# LAMEBOY.net
KiCad netlist of a schematic drawn in EAGLE
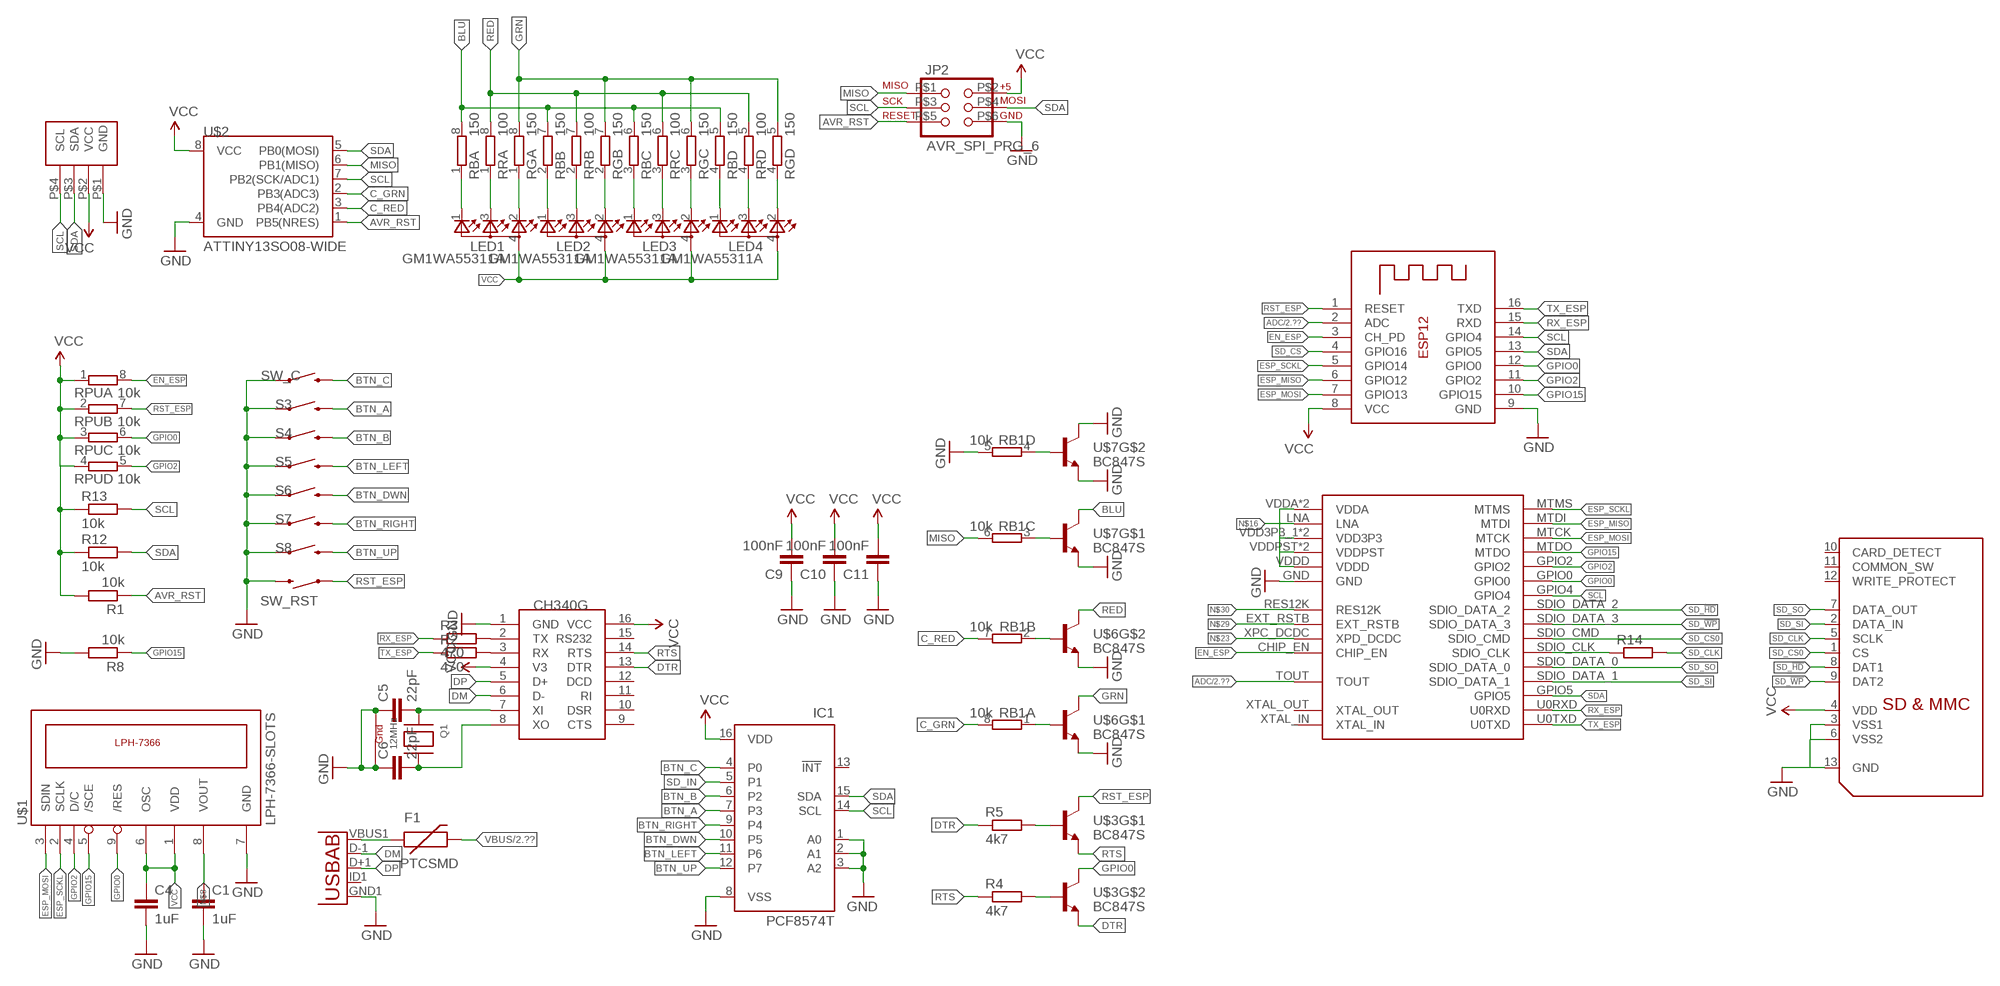
[diagram p0: schematic, sheet 1]
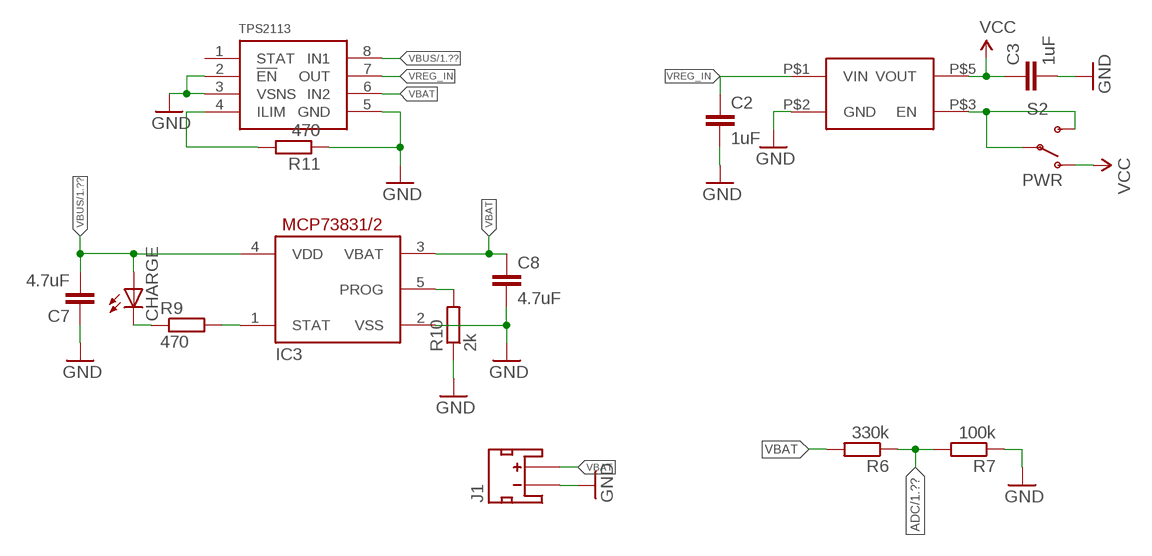
[diagram p1: schematic, sheet 2]

(export (version "E")
  (design (tool "Eeschema 10.0.6"))
  (components
    (comp (ref "C1")
      (value "1uF")
      (footprint "eagle-import:ONEFITSALL")
      (libsource (lib "eagle-import") (part "C-EUONEFITSALL"))
    )
    (comp (ref "C4")
      (value "1uF")
      (footprint "eagle-import:ONEFITSALL")
      (libsource (lib "eagle-import") (part "C-EUONEFITSALL"))
    )
    (comp (ref "C5")
      (value "22pF")
      (footprint "eagle-import:ONEFITSALL")
      (libsource (lib "eagle-import") (part "C-EUONEFITSALL"))
    )
    (comp (ref "C6")
      (value "22pF")
      (footprint "eagle-import:ONEFITSALL")
      (libsource (lib "eagle-import") (part "C-EUONEFITSALL"))
    )
    (comp (ref "C9")
      (value "100nF")
      (footprint "eagle-import:ONEFITSALL")
      (libsource (lib "eagle-import") (part "C-EUONEFITSALL"))
    )
    (comp (ref "C10")
      (value "100nF")
      (footprint "eagle-import:ONEFITSALL")
      (libsource (lib "eagle-import") (part "C-EUONEFITSALL"))
    )
    (comp (ref "C11")
      (value "100nF")
      (footprint "eagle-import:ONEFITSALL")
      (libsource (lib "eagle-import") (part "C-EUONEFITSALL"))
    )
    (comp (ref "CH340G")
      (value "CH340GCH340G")
      (footprint "eagle-import:SOIC16")
      (libsource (lib "eagle-import") (part "CH340GCH340G"))
    )
    (comp (ref "F1")
      (value "PTCSMD")
      (footprint "eagle-import:PTC-1206")
      (libsource (lib "eagle-import") (part "PTCSMD"))
    )
    (comp (ref "IC1")
      (value "PCF8574T")
      (footprint "eagle-import:SO16W")
      (fields (field (name "MPN") "PCF8574T/3,512"))
      (libsource (lib "eagle-import") (part "PCF8574T"))
    )
    (comp (ref "JP2")
      (value "AVR_SPI_PRG_6")
      (footprint "eagle-import:2X3_SMD_PAD")
      (libsource (lib "eagle-import") (part "AVR_SPI_PRG_6"))
    )
    (comp (ref "LED1")
      (value "GM1WA55311A")
      (footprint "eagle-import:GM1WA55311A")
      (libsource (lib "eagle-import") (part "GM1WA55311A"))
    )
    (comp (ref "LED2")
      (value "GM1WA55311A")
      (footprint "eagle-import:GM1WA55311A")
      (libsource (lib "eagle-import") (part "GM1WA55311A"))
    )
    (comp (ref "LED3")
      (value "GM1WA55311A")
      (footprint "eagle-import:GM1WA55311A")
      (libsource (lib "eagle-import") (part "GM1WA55311A"))
    )
    (comp (ref "LED4")
      (value "GM1WA55311A")
      (footprint "eagle-import:GM1WA55311A")
      (libsource (lib "eagle-import") (part "GM1WA55311A"))
    )
    (comp (ref "Q1")
      (value "12MHz")
      (footprint "eagle-import:NX3225_BIGGER")
      (libsource (lib "eagle-import") (part "XTAL-4BIGGER"))
    )
    (comp (ref "R1")
      (value "10k")
      (footprint "eagle-import:ONEFITSALL")
      (libsource (lib "eagle-import") (part "R-EU_ONEFITSALL"))
    )
    (comp (ref "R2")
      (value "470")
      (footprint "eagle-import:ONEFITSALL")
      (libsource (lib "eagle-import") (part "R-EU_ONEFITSALL"))
    )
    (comp (ref "R3")
      (value "470")
      (footprint "eagle-import:ONEFITSALL")
      (libsource (lib "eagle-import") (part "R-EU_ONEFITSALL"))
    )
    (comp (ref "R4")
      (value "4k7")
      (footprint "eagle-import:ONEFITSALL")
      (libsource (lib "eagle-import") (part "R-EU_ONEFITSALL"))
    )
    (comp (ref "R5")
      (value "4k7")
      (footprint "eagle-import:ONEFITSALL")
      (libsource (lib "eagle-import") (part "R-EU_ONEFITSALL"))
    )
    (comp (ref "R8")
      (value "10k")
      (footprint "eagle-import:ONEFITSALL")
      (libsource (lib "eagle-import") (part "R-EU_ONEFITSALL"))
    )
    (comp (ref "R12")
      (value "10k")
      (footprint "eagle-import:ONEFITSALL")
      (libsource (lib "eagle-import") (part "R-EU_ONEFITSALL"))
    )
    (comp (ref "R13")
      (value "10k")
      (footprint "eagle-import:ONEFITSALL")
      (libsource (lib "eagle-import") (part "R-EU_ONEFITSALL"))
    )
    (comp (ref "R14")
      (value "R-EU_R0603")
      (footprint "eagle-import:R0603")
      (libsource (lib "eagle-import") (part "R-EU_R0603"))
    )
    (comp (ref "RB")
      (value "150")
      (footprint "eagle-import:0603-ARC")
      (libsource (lib "eagle-import") (part "4R-N0603-ARC"))
    )
    (comp (ref "RB1")
      (value "10k")
      (footprint "eagle-import:0603-ARC")
      (libsource (lib "eagle-import") (part "4R-N0603-ARC"))
    )
    (comp (ref "RG")
      (value "150")
      (footprint "eagle-import:0603-ARC")
      (libsource (lib "eagle-import") (part "4R-N0603-ARC"))
    )
    (comp (ref "RPU")
      (value "10k")
      (footprint "eagle-import:0603-ARC")
      (libsource (lib "eagle-import") (part "4R-N0603-ARC"))
    )
    (comp (ref "RR")
      (value "100")
      (footprint "eagle-import:0603-ARC")
      (libsource (lib "eagle-import") (part "4R-N0603-ARC"))
    )
    (comp (ref "S3")
      (value "SWITCH-MOMENTARY-2SMD-4")
      (footprint "eagle-import:TACTILE_SWITCH_TALL")
      (libsource (lib "eagle-import") (part "SWITCH-MOMENTARY-2SMD-4"))
    )
    (comp (ref "S4")
      (value "SWITCH-MOMENTARY-2SMD-4")
      (footprint "eagle-import:TACTILE_SWITCH_TALL")
      (libsource (lib "eagle-import") (part "SWITCH-MOMENTARY-2SMD-4"))
    )
    (comp (ref "S5")
      (value "SWITCH-MOMENTARY-2SMD-4")
      (footprint "eagle-import:TACTILE_SWITCH_TALL")
      (libsource (lib "eagle-import") (part "SWITCH-MOMENTARY-2SMD-4"))
    )
    (comp (ref "S6")
      (value "SWITCH-MOMENTARY-2SMD-4")
      (footprint "eagle-import:TACTILE_SWITCH_TALL")
      (libsource (lib "eagle-import") (part "SWITCH-MOMENTARY-2SMD-4"))
    )
    (comp (ref "S7")
      (value "SWITCH-MOMENTARY-2SMD-4")
      (footprint "eagle-import:TACTILE_SWITCH_TALL")
      (libsource (lib "eagle-import") (part "SWITCH-MOMENTARY-2SMD-4"))
    )
    (comp (ref "S8")
      (value "SWITCH-MOMENTARY-2SMD-4")
      (footprint "eagle-import:TACTILE_SWITCH_TALL")
      (libsource (lib "eagle-import") (part "SWITCH-MOMENTARY-2SMD-4"))
    )
    (comp (ref "SW_C")
      (value "SWITCH-MOMENTARY-2-SMD-1101NE")
      (footprint "eagle-import:TACTILE-SWITCH-1101NE")
      (libsource (lib "eagle-import") (part "SWITCH-MOMENTARY-2-SMD-1101NE"))
    )
    (comp (ref "SW_RST")
      (value "SWITCH-MOMENTARY-2-SMD-1101NE")
      (footprint "eagle-import:TACTILE-SWITCH-1101NE")
      (libsource (lib "eagle-import") (part "SWITCH-MOMENTARY-2-SMD-1101NE"))
    )
    (comp (ref "U$1")
      (value "LPH-7366-SLOTS")
      (footprint "eagle-import:LPH-7366-SLOTS")
      (libsource (lib "eagle-import") (part "LPH-7366-SLOTS"))
    )
    (comp (ref "U$2")
      (value "ATTINY13SO08-WIDE")
      (footprint "eagle-import:SO08-EIAJ")
      (libsource (lib "eagle-import") (part "ATTINY13SO08-WIDE"))
    )
    (comp (ref "U$3")
      (value "BC847S")
      (footprint "eagle-import:SOT363")
      (libsource (lib "eagle-import") (part "MMDT3904"))
    )
    (comp (ref "U$6")
      (value "BC847S")
      (footprint "eagle-import:SOT363")
      (libsource (lib "eagle-import") (part "MMDT3904"))
    )
    (comp (ref "U$7")
      (value "BC847S")
      (footprint "eagle-import:SOT363")
      (libsource (lib "eagle-import") (part "MMDT3904"))
    )
    (comp (ref "U$10")
      (value "I2C_GROVE")
      (footprint "eagle-import:I2C_GROVE")
      (libsource (lib "eagle-import") (part "I2C_GROVE"))
    )
    (comp (ref "U$13")
      (value "ESP8266EX")
      (footprint "eagle-import:ESP8266EX")
      (libsource (lib "eagle-import") (part "ESP8266EX"))
    )
    (comp (ref "U$14")
      (value "SDMMCSCDA")
      (footprint "eagle-import:SCDA")
      (libsource (lib "eagle-import") (part "SDMMCSCDA"))
    )
    (comp (ref "U2")
      (value "USB")
      (footprint "eagle-import:USB-AB-MICRO-SMD_V03")
      (libsource (lib "eagle-import") (part "USB-ABCONN-11794"))
    )
    (comp (ref "X1")
      (value "ESP-12")
      (footprint "eagle-import:ESP-12")
      (libsource (lib "eagle-import") (part "ESP-12"))
    )
    (comp (ref "C2")
      (value "1uF")
      (footprint "eagle-import:ONEFITSALL")
      (libsource (lib "eagle-import") (part "C-EUONEFITSALL"))
    )
    (comp (ref "C3")
      (value "1uF")
      (footprint "eagle-import:ONEFITSALL")
      (libsource (lib "eagle-import") (part "C-EUONEFITSALL"))
    )
    (comp (ref "C7")
      (value "4.7uF")
      (footprint "eagle-import:ONEFITSALL")
      (libsource (lib "eagle-import") (part "C-EUONEFITSALL"))
    )
    (comp (ref "C8")
      (value "4.7uF")
      (footprint "eagle-import:ONEFITSALL")
      (libsource (lib "eagle-import") (part "C-EUONEFITSALL"))
    )
    (comp (ref "CHARGE")
      (value "LEDCHIP-LED0805")
      (footprint "eagle-import:CHIP-LED0805")
      (libsource (lib "eagle-import") (part "LEDCHIP-LED0805"))
    )
    (comp (ref "IC3")
      (value "MCP73831")
      (footprint "eagle-import:SOT23-5L")
      (libsource (lib "eagle-import") (part "MCP73831/OT"))
    )
    (comp (ref "J1")
      (value "JST_2MM_MALE")
      (footprint "eagle-import:JST-2-SMD")
      (libsource (lib "eagle-import") (part "JST_2MM_MALE"))
    )
    (comp (ref "R6")
      (value "330k")
      (footprint "eagle-import:ONEFITSALL")
      (libsource (lib "eagle-import") (part "R-EU_ONEFITSALL"))
    )
    (comp (ref "R7")
      (value "100k")
      (footprint "eagle-import:ONEFITSALL")
      (libsource (lib "eagle-import") (part "R-EU_ONEFITSALL"))
    )
    (comp (ref "R9")
      (value "470")
      (footprint "eagle-import:ONEFITSALL")
      (libsource (lib "eagle-import") (part "R-EU_ONEFITSALL"))
    )
    (comp (ref "R10")
      (value "2k")
      (footprint "eagle-import:ONEFITSALL")
      (libsource (lib "eagle-import") (part "R-EU_ONEFITSALL"))
    )
    (comp (ref "R11")
      (value "470")
      (footprint "eagle-import:ONEFITSALL")
      (libsource (lib "eagle-import") (part "R-EU_ONEFITSALL"))
    )
    (comp (ref "S2")
      (value "PWR")
      (footprint "eagle-import:SWITCH-SPST-SMD-A")
      (libsource (lib "eagle-import") (part "SWITCH-SPDT-SMD-A"))
    )
    (comp (ref "U$4")
      (value "TPS2113-PW")
      (footprint "eagle-import:TEXAS-PW")
      (libsource (lib "eagle-import") (part "TPS2113-PW"))
    )
    (comp (ref "U$9")
      (value "AP2112KAP2112K")
      (footprint "eagle-import:AP2112")
      (libsource (lib "eagle-import") (part "AP2112KAP2112K"))
    )
  )
  (nets
    (net (code "1") (name "ADC") (class "Default")
      (node (ref "R6") (pin "P$1") (pinfunction "1_P$1") (pintype "passive"))
      (node (ref "R7") (pin "P$2") (pinfunction "2_P$2") (pintype "passive"))
      (node (ref "U$13") (pin "TOUT") (pinfunction "TOUT_TOUT") (pintype "bidirectional"))
      (node (ref "X1") (pin "2") (pinfunction "ADC_2") (pintype "passive"))
    )
    (net (code "2") (name "AVR_RST") (class "Default")
      (node (ref "JP2") (pin "P$5") (pinfunction "5_P$5") (pintype "passive"))
      (node (ref "R1") (pin "P$1") (pinfunction "1_P$1") (pintype "passive"))
      (node (ref "U$2") (pin "1") (pinfunction "PB5(NRES)_1") (pintype "bidirectional"))
    )
    (net (code "3") (name "BLU") (class "Default")
      (node (ref "RB") (pin "5") (pinfunction "2_5") (pintype "passive"))
      (node (ref "RB") (pin "6") (pinfunction "2_6") (pintype "passive"))
      (node (ref "RB") (pin "7") (pinfunction "2_7") (pintype "passive"))
      (node (ref "RB") (pin "8") (pinfunction "2_8") (pintype "passive"))
      (node (ref "U$7") (pin "3") (pinfunction "C_3") (pintype "passive"))
    )
    (net (code "4") (name "BTN_A") (class "Default")
      (node (ref "IC1") (pin "7") (pinfunction "P3_7") (pintype "bidirectional"))
      (node (ref "S3") (pin "B2") (pinfunction "2_B2") (pintype "passive"))
    )
    (net (code "5") (name "BTN_B") (class "Default")
      (node (ref "IC1") (pin "6") (pinfunction "P2_6") (pintype "bidirectional"))
      (node (ref "S4") (pin "B2") (pinfunction "2_B2") (pintype "passive"))
    )
    (net (code "6") (name "BTN_C") (class "Default")
      (node (ref "IC1") (pin "4") (pinfunction "P0_4") (pintype "bidirectional"))
      (node (ref "SW_C") (pin "P$2") (pinfunction "2_P$2") (pintype "passive"))
    )
    (net (code "7") (name "BTN_DWN") (class "Default")
      (node (ref "IC1") (pin "10") (pinfunction "P5_10") (pintype "bidirectional"))
      (node (ref "S6") (pin "B2") (pinfunction "2_B2") (pintype "passive"))
    )
    (net (code "8") (name "BTN_LEFT") (class "Default")
      (node (ref "IC1") (pin "11") (pinfunction "P6_11") (pintype "bidirectional"))
      (node (ref "S5") (pin "B2") (pinfunction "2_B2") (pintype "passive"))
    )
    (net (code "9") (name "BTN_RIGHT") (class "Default")
      (node (ref "IC1") (pin "9") (pinfunction "P4_9") (pintype "bidirectional"))
      (node (ref "S7") (pin "B2") (pinfunction "2_B2") (pintype "passive"))
    )
    (net (code "10") (name "BTN_UP") (class "Default")
      (node (ref "IC1") (pin "12") (pinfunction "P7_12") (pintype "bidirectional"))
      (node (ref "S8") (pin "B2") (pinfunction "2_B2") (pintype "passive"))
    )
    (net (code "11") (name "C_GRN") (class "Default")
      (node (ref "RB1") (pin "8") (pinfunction "2_8") (pintype "passive"))
      (node (ref "U$2") (pin "2") (pinfunction "PB3(ADC3)_2") (pintype "bidirectional"))
    )
    (net (code "12") (name "C_RED") (class "Default")
      (node (ref "RB1") (pin "7") (pinfunction "2_7") (pintype "passive"))
      (node (ref "U$2") (pin "3") (pinfunction "PB4(ADC2)_3") (pintype "bidirectional"))
    )
    (net (code "13") (name "DM") (class "Default")
      (node (ref "CH340G") (pin "6") (pinfunction "D-_6") (pintype "bidirectional"))
      (node (ref "U2") (pin "D-1") (pinfunction "D-_D-1") (pintype "bidirectional"))
    )
    (net (code "14") (name "DP") (class "Default")
      (node (ref "CH340G") (pin "5") (pinfunction "D+_5") (pintype "bidirectional"))
      (node (ref "U2") (pin "D+1") (pinfunction "D+_D+1") (pintype "bidirectional"))
    )
    (net (code "15") (name "DTR") (class "Default")
      (node (ref "CH340G") (pin "13") (pinfunction "DTR_13") (pintype "bidirectional"))
      (node (ref "R5") (pin "P$1") (pinfunction "1_P$1") (pintype "passive"))
      (node (ref "U$3") (pin "1") (pinfunction "E_1") (pintype "passive"))
    )
    (net (code "16") (name "EN_ESP") (class "Default")
      (node (ref "RPU") (pin "8") (pinfunction "2_8") (pintype "passive"))
      (node (ref "U$13") (pin "CHIP_EN") (pinfunction "CHIP_EN_CHIP_EN") (pintype "bidirectional"))
      (node (ref "X1") (pin "3") (pinfunction "CH_PD_3") (pintype "input"))
    )
    (net (code "17") (name "ESP_MISO") (class "Default")
      (node (ref "U$13") (pin "MTDI") (pinfunction "MTDI_MTDI") (pintype "bidirectional"))
      (node (ref "X1") (pin "6") (pinfunction "GPIO12_6") (pintype "bidirectional"))
    )
    (net (code "18") (name "ESP_MOSI") (class "Default")
      (node (ref "U$1") (pin "3") (pinfunction "SDIN_3") (pintype "input"))
      (node (ref "U$13") (pin "MTCK") (pinfunction "MTCK_MTCK") (pintype "bidirectional"))
      (node (ref "X1") (pin "7") (pinfunction "GPIO13_7") (pintype "bidirectional"))
    )
    (net (code "19") (name "ESP_SCKL") (class "Default")
      (node (ref "U$1") (pin "2") (pinfunction "SCLK_2") (pintype "input"))
      (node (ref "U$13") (pin "MTMS") (pinfunction "MTMS_MTMS") (pintype "bidirectional"))
      (node (ref "X1") (pin "5") (pinfunction "GPIO14_5") (pintype "bidirectional"))
    )
    (net (code "20") (name "GND") (class "Default")
      (node (ref "C1") (pin "P$2") (pinfunction "2_P$2") (pintype "passive"))
      (node (ref "C10") (pin "P$1") (pinfunction "1_P$1") (pintype "passive"))
      (node (ref "C11") (pin "P$1") (pinfunction "1_P$1") (pintype "passive"))
      (node (ref "C2") (pin "P$2") (pinfunction "2_P$2") (pintype "passive"))
      (node (ref "C3") (pin "P$2") (pinfunction "2_P$2") (pintype "passive"))
      (node (ref "C4") (pin "P$2") (pinfunction "2_P$2") (pintype "passive"))
      (node (ref "C5") (pin "P$1") (pinfunction "1_P$1") (pintype "passive"))
      (node (ref "C6") (pin "P$1") (pinfunction "1_P$1") (pintype "passive"))
      (node (ref "C7") (pin "P$1") (pinfunction "1_P$1") (pintype "passive"))
      (node (ref "C8") (pin "P$2") (pinfunction "2_P$2") (pintype "passive"))
      (node (ref "C9") (pin "P$1") (pinfunction "1_P$1") (pintype "passive"))
      (node (ref "CH340G") (pin "1") (pinfunction "GND_1") (pintype "bidirectional"))
      (node (ref "IC1") (pin "1") (pinfunction "A0_1") (pintype "input"))
      (node (ref "IC1") (pin "2") (pinfunction "A1_2") (pintype "input"))
      (node (ref "IC1") (pin "3") (pinfunction "A2_3") (pintype "input"))
      (node (ref "IC1") (pin "8") (pinfunction "VSS_8") (pintype "power_in"))
      (node (ref "IC3") (pin "2") (pinfunction "VSS_2") (pintype "power_in"))
      (node (ref "J1") (pin "1") (pinfunction "-_1") (pintype "bidirectional"))
      (node (ref "JP2") (pin "P$6") (pinfunction "6_P$6") (pintype "passive"))
      (node (ref "Q1") (pin "2") (pinfunction "G2_2") (pintype "power_in"))
      (node (ref "Q1") (pin "4") (pinfunction "G1_4") (pintype "power_in"))
      (node (ref "R10") (pin "P$1") (pinfunction "1_P$1") (pintype "passive"))
      (node (ref "R11") (pin "P$1") (pinfunction "1_P$1") (pintype "passive"))
      (node (ref "R7") (pin "P$1") (pinfunction "1_P$1") (pintype "passive"))
      (node (ref "R8") (pin "P$2") (pinfunction "2_P$2") (pintype "passive"))
      (node (ref "RB1") (pin "5") (pinfunction "2_5") (pintype "passive"))
      (node (ref "S3") (pin "A2") (pinfunction "1_A2") (pintype "passive"))
      (node (ref "S4") (pin "A2") (pinfunction "1_A2") (pintype "passive"))
      (node (ref "S5") (pin "A2") (pinfunction "1_A2") (pintype "passive"))
      (node (ref "S6") (pin "A2") (pinfunction "1_A2") (pintype "passive"))
      (node (ref "S7") (pin "A2") (pinfunction "1_A2") (pintype "passive"))
      (node (ref "S8") (pin "A2") (pinfunction "1_A2") (pintype "passive"))
      (node (ref "SW_C") (pin "P$1") (pinfunction "1_P$1") (pintype "passive"))
      (node (ref "SW_RST") (pin "P$2") (pinfunction "2_P$2") (pintype "passive"))
      (node (ref "U$1") (pin "7") (pinfunction "GND_7") (pintype "power_in"))
      (node (ref "U$10") (pin "P$1") (pinfunction "GND_P$1") (pintype "bidirectional"))
      (node (ref "U$13") (pin "GND") (pinfunction "GND_GND") (pintype "bidirectional"))
      (node (ref "U$14") (pin "13") (pinfunction "GND_13") (pintype "power_in"))
      (node (ref "U$14") (pin "3") (pinfunction "VSS1_3") (pintype "power_in"))
      (node (ref "U$14") (pin "6") (pinfunction "VSS2_6") (pintype "power_in"))
      (node (ref "U$2") (pin "4") (pinfunction "GND_4") (pintype "bidirectional"))
      (node (ref "U$4") (pin "2") (pinfunction "~{EN}_2") (pintype "bidirectional"))
      (node (ref "U$4") (pin "3") (pinfunction "VSNS_3") (pintype "bidirectional"))
      (node (ref "U$4") (pin "5") (pinfunction "GND_5") (pintype "bidirectional"))
      (node (ref "U$6") (pin "1") (pinfunction "E_1") (pintype "passive"))
      (node (ref "U$6") (pin "4") (pinfunction "E_4") (pintype "passive"))
      (node (ref "U$7") (pin "1") (pinfunction "E_1") (pintype "passive"))
      (node (ref "U$7") (pin "4") (pinfunction "E_4") (pintype "passive"))
      (node (ref "U$7") (pin "6") (pinfunction "C_6") (pintype "passive"))
      (node (ref "U$9") (pin "P$2") (pinfunction "GND_P$2") (pintype "bidirectional"))
      (node (ref "U2") (pin "GND1") (pinfunction "GND_GND1") (pintype "bidirectional"))
      (node (ref "X1") (pin "9") (pinfunction "GND_9") (pintype "power_in"))
    )
    (net (code "21") (name "GPIO0") (class "Default")
      (node (ref "RPU") (pin "6") (pinfunction "2_6") (pintype "passive"))
      (node (ref "U$1") (pin "9") (pinfunction "/RES_9") (pintype "input"))
      (node (ref "U$13") (pin "GPIO0") (pinfunction "GPIO0_GPIO0") (pintype "bidirectional"))
      (node (ref "U$3") (pin "6") (pinfunction "C_6") (pintype "passive"))
      (node (ref "X1") (pin "12") (pinfunction "GPIO0_12") (pintype "bidirectional"))
    )
    (net (code "22") (name "GPIO2") (class "Default")
      (node (ref "RPU") (pin "5") (pinfunction "2_5") (pintype "passive"))
      (node (ref "U$1") (pin "4") (pinfunction "D/C_4") (pintype "input"))
      (node (ref "U$13") (pin "GPIO2") (pinfunction "GPIO2_GPIO2") (pintype "bidirectional"))
      (node (ref "X1") (pin "11") (pinfunction "GPIO2_11") (pintype "bidirectional"))
    )
    (net (code "23") (name "GPIO15") (class "Default")
      (node (ref "R8") (pin "P$1") (pinfunction "1_P$1") (pintype "passive"))
      (node (ref "U$1") (pin "5") (pinfunction "/SCE_5") (pintype "input"))
      (node (ref "U$13") (pin "MTDO") (pinfunction "MTDO_MTDO") (pintype "bidirectional"))
      (node (ref "X1") (pin "10") (pinfunction "GPIO15_10") (pintype "bidirectional"))
    )
    (net (code "24") (name "GRN") (class "Default")
      (node (ref "RG") (pin "5") (pinfunction "2_5") (pintype "passive"))
      (node (ref "RG") (pin "6") (pinfunction "2_6") (pintype "passive"))
      (node (ref "RG") (pin "7") (pinfunction "2_7") (pintype "passive"))
      (node (ref "RG") (pin "8") (pinfunction "2_8") (pintype "passive"))
      (node (ref "U$6") (pin "3") (pinfunction "C_3") (pintype "passive"))
    )
    (net (code "25") (name "MISO") (class "Default")
      (node (ref "JP2") (pin "P$1") (pinfunction "1_P$1") (pintype "passive"))
      (node (ref "RB1") (pin "6") (pinfunction "2_6") (pintype "passive"))
      (node (ref "U$2") (pin "6") (pinfunction "PB1(MISO)_6") (pintype "bidirectional"))
    )
    (net (code "26") (name "N$8") (class "Default")
      (node (ref "C1") (pin "P$1") (pinfunction "1_P$1") (pintype "passive"))
      (node (ref "U$1") (pin "8") (pinfunction "VOUT_8") (pintype "passive"))
    )
    (net (code "27") (name "N$16") (class "Default")
      (node (ref "U$13") (pin "LNA") (pinfunction "LNA_LNA") (pintype "bidirectional"))
    )
    (net (code "28") (name "N$23") (class "Default")
      (node (ref "U$13") (pin "XPC_DCDC") (pinfunction "XPD_DCDC_XPC_DCDC") (pintype "bidirectional"))
    )
    (net (code "29") (name "N$29") (class "Default")
      (node (ref "U$13") (pin "EXT_RSTB") (pinfunction "EXT_RSTB_EXT_RSTB") (pintype "bidirectional"))
    )
    (net (code "30") (name "N$30") (class "Default")
      (node (ref "U$13") (pin "RES12K") (pinfunction "RES12K_RES12K") (pintype "bidirectional"))
    )
    (net (code "31") (name "Net-(C5-2)") (class "Default")
      (node (ref "C5") (pin "P$2") (pinfunction "2_P$2") (pintype "passive"))
      (node (ref "CH340G") (pin "7") (pinfunction "XI_7") (pintype "bidirectional"))
      (node (ref "Q1") (pin "1") (pinfunction "X1_1") (pintype "bidirectional"))
    )
    (net (code "32") (name "Net-(C6-2)") (class "Default")
      (node (ref "C6") (pin "P$2") (pinfunction "2_P$2") (pintype "passive"))
      (node (ref "CH340G") (pin "8") (pinfunction "XO_8") (pintype "bidirectional"))
      (node (ref "Q1") (pin "3") (pinfunction "X2_3") (pintype "bidirectional"))
    )
    (net (code "33") (name "Net-(CH340G-RX)") (class "Default")
      (node (ref "CH340G") (pin "3") (pinfunction "RX_3") (pintype "bidirectional"))
      (node (ref "R2") (pin "P$2") (pinfunction "2_P$2") (pintype "passive"))
    )
    (net (code "34") (name "Net-(CH340G-TX)") (class "Default")
      (node (ref "CH340G") (pin "2") (pinfunction "TX_2") (pintype "bidirectional"))
      (node (ref "R3") (pin "P$2") (pinfunction "2_P$2") (pintype "passive"))
    )
    (net (code "35") (name "Net-(IC3-PROG)") (class "Default")
      (node (ref "IC3") (pin "5") (pinfunction "PROG_5") (pintype "input"))
      (node (ref "R10") (pin "P$2") (pinfunction "2_P$2") (pintype "passive"))
    )
    (net (code "36") (name "Net-(IC3-STAT)") (class "Default")
      (node (ref "IC3") (pin "1") (pinfunction "STAT_1") (pintype "output"))
      (node (ref "R9") (pin "P$2") (pinfunction "2_P$2") (pintype "passive"))
    )
    (net (code "37") (name "Net-(LED1-CBLUE)") (class "Default")
      (node (ref "LED1") (pin "3") (pinfunction "CBLUE_3") (pintype "passive"))
      (node (ref "RR") (pin "1") (pinfunction "1_1") (pintype "passive"))
    )
    (net (code "38") (name "Net-(LED1-CGREEN)") (class "Default")
      (node (ref "LED1") (pin "1") (pinfunction "CGREEN_1") (pintype "passive"))
      (node (ref "RB") (pin "1") (pinfunction "1_1") (pintype "passive"))
    )
    (net (code "39") (name "Net-(LED1-CRED)") (class "Default")
      (node (ref "LED1") (pin "2") (pinfunction "CRED_2") (pintype "passive"))
      (node (ref "RG") (pin "1") (pinfunction "1_1") (pintype "passive"))
    )
    (net (code "40") (name "Net-(LED2-CBLUE)") (class "Default")
      (node (ref "LED2") (pin "3") (pinfunction "CBLUE_3") (pintype "passive"))
      (node (ref "RR") (pin "2") (pinfunction "1_2") (pintype "passive"))
    )
    (net (code "41") (name "Net-(LED2-CGREEN)") (class "Default")
      (node (ref "LED2") (pin "1") (pinfunction "CGREEN_1") (pintype "passive"))
      (node (ref "RB") (pin "2") (pinfunction "1_2") (pintype "passive"))
    )
    (net (code "42") (name "Net-(LED2-CRED)") (class "Default")
      (node (ref "LED2") (pin "2") (pinfunction "CRED_2") (pintype "passive"))
      (node (ref "RG") (pin "2") (pinfunction "1_2") (pintype "passive"))
    )
    (net (code "43") (name "Net-(LED3-CBLUE)") (class "Default")
      (node (ref "LED3") (pin "3") (pinfunction "CBLUE_3") (pintype "passive"))
      (node (ref "RR") (pin "3") (pinfunction "1_3") (pintype "passive"))
    )
    (net (code "44") (name "Net-(LED3-CGREEN)") (class "Default")
      (node (ref "LED3") (pin "1") (pinfunction "CGREEN_1") (pintype "passive"))
      (node (ref "RB") (pin "3") (pinfunction "1_3") (pintype "passive"))
    )
    (net (code "45") (name "Net-(LED3-CRED)") (class "Default")
      (node (ref "LED3") (pin "2") (pinfunction "CRED_2") (pintype "passive"))
      (node (ref "RG") (pin "3") (pinfunction "1_3") (pintype "passive"))
    )
    (net (code "46") (name "Net-(LED4-CBLUE)") (class "Default")
      (node (ref "LED4") (pin "3") (pinfunction "CBLUE_3") (pintype "passive"))
      (node (ref "RR") (pin "4") (pinfunction "1_4") (pintype "passive"))
    )
    (net (code "47") (name "Net-(LED4-CGREEN)") (class "Default")
      (node (ref "LED4") (pin "1") (pinfunction "CGREEN_1") (pintype "passive"))
      (node (ref "RB") (pin "4") (pinfunction "1_4") (pintype "passive"))
    )
    (net (code "48") (name "Net-(LED4-CRED)") (class "Default")
      (node (ref "LED4") (pin "2") (pinfunction "CRED_2") (pintype "passive"))
      (node (ref "RG") (pin "4") (pinfunction "1_4") (pintype "passive"))
    )
    (net (code "49") (name "Net-(R4-2)") (class "Default")
      (node (ref "R4") (pin "P$2") (pinfunction "2_P$2") (pintype "passive"))
      (node (ref "U$3") (pin "2") (pinfunction "B_2") (pintype "passive"))
    )
    (net (code "50") (name "Net-(R5-2)") (class "Default")
      (node (ref "R5") (pin "P$2") (pinfunction "2_P$2") (pintype "passive"))
      (node (ref "U$3") (pin "5") (pinfunction "B_5") (pintype "passive"))
    )
    (net (code "51") (name "Net-(R9-1)") (class "Default")
      (node (ref "CHARGE") (pin "C") (pinfunction "C_C") (pintype "passive"))
      (node (ref "R9") (pin "P$1") (pinfunction "1_P$1") (pintype "passive"))
    )
    (net (code "52") (name "Net-(R11-2)") (class "Default")
      (node (ref "R11") (pin "P$2") (pinfunction "2_P$2") (pintype "passive"))
      (node (ref "U$4") (pin "4") (pinfunction "ILIM_4") (pintype "bidirectional"))
    )
    (net (code "53") (name "Net-(R14-Pad1)") (class "Default")
      (node (ref "R14") (pin "1") (pinfunction "1_1") (pintype "passive"))
      (node (ref "U$13") (pin "SDIO_CLK") (pinfunction "SDIO_CLK_SDIO_CLK") (pintype "bidirectional"))
    )
    (net (code "54") (name "Net-(RB1B-1)") (class "Default")
      (node (ref "RB1") (pin "2") (pinfunction "1_2") (pintype "passive"))
      (node (ref "U$6") (pin "2") (pinfunction "B_2") (pintype "passive"))
    )
    (net (code "55") (name "Net-(RB1C-1)") (class "Default")
      (node (ref "RB1") (pin "3") (pinfunction "1_3") (pintype "passive"))
      (node (ref "U$7") (pin "5") (pinfunction "B_5") (pintype "passive"))
    )
    (net (code "56") (name "Net-(RB1D-1)") (class "Default")
      (node (ref "RB1") (pin "4") (pinfunction "1_4") (pintype "passive"))
      (node (ref "U$7") (pin "2") (pinfunction "B_2") (pintype "passive"))
    )
    (net (code "57") (name "Net-(S2-P)") (class "Default")
      (node (ref "S2") (pin "2") (pinfunction "P_2") (pintype "passive"))
      (node (ref "S2") (pin "3") (pinfunction "S_3") (pintype "passive"))
      (node (ref "U$9") (pin "P$3") (pinfunction "EN_P$3") (pintype "bidirectional"))
    )
    (net (code "58") (name "Net-(U$6A-B)") (class "Default")
      (node (ref "RB1") (pin "1") (pinfunction "1_1") (pintype "passive"))
      (node (ref "U$6") (pin "5") (pinfunction "B_5") (pintype "passive"))
    )
    (net (code "59") (name "Net-(U$13-PadVDDA)") (class "Default")
      (node (ref "U$13") (pin "VDD3P3_1") (pinfunction "VDD3P3_VDD3P3_1") (pintype "bidirectional"))
      (node (ref "U$13") (pin "VDD3P3_2") (pinfunction "VDD3P3_VDD3P3_2") (pintype "bidirectional"))
      (node (ref "U$13") (pin "VDDA") (pinfunction "VDDA_VDDA") (pintype "bidirectional"))
      (node (ref "U$13") (pin "VDDA_2") (pinfunction "VDDA_VDDA_2") (pintype "bidirectional"))
      (node (ref "U$13") (pin "VDDD") (pinfunction "VDDD_VDDD") (pintype "bidirectional"))
      (node (ref "U$13") (pin "VDDPST") (pinfunction "VDDPST_VDDPST") (pintype "bidirectional"))
      (node (ref "U$13") (pin "VDDPST_2") (pinfunction "VDDPST_VDDPST_2") (pintype "bidirectional"))
    )
    (net (code "60") (name "Net-(U2-VBUS)") (class "Default")
      (node (ref "F1") (pin "1") (pinfunction "1_1") (pintype "bidirectional"))
      (node (ref "U2") (pin "VBUS1") (pinfunction "VBUS_VBUS1") (pintype "bidirectional"))
    )
    (net (code "61") (name "RED") (class "Default")
      (node (ref "RR") (pin "5") (pinfunction "2_5") (pintype "passive"))
      (node (ref "RR") (pin "6") (pinfunction "2_6") (pintype "passive"))
      (node (ref "RR") (pin "7") (pinfunction "2_7") (pintype "passive"))
      (node (ref "RR") (pin "8") (pinfunction "2_8") (pintype "passive"))
      (node (ref "U$6") (pin "6") (pinfunction "C_6") (pintype "passive"))
    )
    (net (code "62") (name "RST_ESP") (class "Default")
      (node (ref "RPU") (pin "7") (pinfunction "2_7") (pintype "passive"))
      (node (ref "SW_RST") (pin "P$1") (pinfunction "1_P$1") (pintype "passive"))
      (node (ref "U$3") (pin "3") (pinfunction "C_3") (pintype "passive"))
      (node (ref "X1") (pin "1") (pinfunction "RESET_1") (pintype "input"))
    )
    (net (code "63") (name "RTS") (class "Default")
      (node (ref "CH340G") (pin "14") (pinfunction "RTS_14") (pintype "bidirectional"))
      (node (ref "R4") (pin "P$1") (pinfunction "1_P$1") (pintype "passive"))
      (node (ref "U$3") (pin "4") (pinfunction "E_4") (pintype "passive"))
    )
    (net (code "64") (name "RX_ESP") (class "Default")
      (node (ref "R3") (pin "P$1") (pinfunction "1_P$1") (pintype "passive"))
      (node (ref "U$13") (pin "U0RXD") (pinfunction "U0RXD_U0RXD") (pintype "bidirectional"))
      (node (ref "X1") (pin "15") (pinfunction "RXD_15") (pintype "input"))
    )
    (net (code "65") (name "SCL") (class "Default")
      (node (ref "IC1") (pin "14") (pinfunction "SCL_14") (pintype "input"))
      (node (ref "JP2") (pin "P$3") (pinfunction "3_P$3") (pintype "passive"))
      (node (ref "R13") (pin "P$2") (pinfunction "2_P$2") (pintype "passive"))
      (node (ref "U$10") (pin "P$4") (pinfunction "SCL_P$4") (pintype "bidirectional"))
      (node (ref "U$13") (pin "GPIO4") (pinfunction "GPIO4_GPIO4") (pintype "bidirectional"))
      (node (ref "U$2") (pin "7") (pinfunction "PB2(SCK/ADC1)_7") (pintype "bidirectional"))
      (node (ref "X1") (pin "14") (pinfunction "GPIO4_14") (pintype "bidirectional"))
    )
    (net (code "66") (name "SDA") (class "Default")
      (node (ref "IC1") (pin "15") (pinfunction "SDA_15") (pintype "bidirectional"))
      (node (ref "JP2") (pin "P$4") (pinfunction "4_P$4") (pintype "passive"))
      (node (ref "R12") (pin "P$2") (pinfunction "2_P$2") (pintype "passive"))
      (node (ref "U$10") (pin "P$3") (pinfunction "SDA_P$3") (pintype "bidirectional"))
      (node (ref "U$13") (pin "GPIO5") (pinfunction "GPIO5_GPIO5") (pintype "bidirectional"))
      (node (ref "U$2") (pin "5") (pinfunction "PB0(MOSI)_5") (pintype "bidirectional"))
      (node (ref "X1") (pin "13") (pinfunction "GPIO5_13") (pintype "bidirectional"))
    )
    (net (code "67") (name "SD_CLK") (class "Default")
      (node (ref "R14") (pin "2") (pinfunction "2_2") (pintype "passive"))
      (node (ref "U$14") (pin "5") (pinfunction "SCLK_5") (pintype "input"))
    )
    (net (code "68") (name "SD_CS") (class "Default")
      (node (ref "X1") (pin "4") (pinfunction "GPIO16_4") (pintype "bidirectional"))
    )
    (net (code "69") (name "SD_CS0") (class "Default")
      (node (ref "U$13") (pin "SDIO_CMD") (pinfunction "SDIO_CMD_SDIO_CMD") (pintype "bidirectional"))
      (node (ref "U$14") (pin "1") (pinfunction "CS_1") (pintype "input"))
    )
    (net (code "70") (name "SD_IN") (class "Default")
      (node (ref "IC1") (pin "5") (pinfunction "P1_5") (pintype "bidirectional"))
    )
    (net (code "71") (name "SD_SI") (class "Default")
      (node (ref "U$13") (pin "SDIO_DATA_1") (pinfunction "SDIO_DATA_1_SDIO_DATA_1") (pintype "bidirectional"))
      (node (ref "U$14") (pin "2") (pinfunction "DATA_IN_2") (pintype "input"))
    )
    (net (code "72") (name "SD_SO") (class "Default")
      (node (ref "U$13") (pin "SDIO_DATA_0") (pinfunction "SDIO_DATA_0_SDIO_DATA_0") (pintype "bidirectional"))
      (node (ref "U$14") (pin "7") (pinfunction "DATA_OUT_7") (pintype "output"))
    )
    (net (code "73") (name "SD_~{HD}") (class "Default")
      (node (ref "U$13") (pin "SDIO_DATA_2") (pinfunction "SDIO_DATA_2_SDIO_DATA_2") (pintype "bidirectional"))
      (node (ref "U$14") (pin "8") (pinfunction "DAT1_8") (pintype "bidirectional"))
    )
    (net (code "74") (name "SD_~{WP}") (class "Default")
      (node (ref "U$13") (pin "SDIO_DATA_3") (pinfunction "SDIO_DATA_3_SDIO_DATA_3") (pintype "bidirectional"))
      (node (ref "U$14") (pin "9") (pinfunction "DAT2_9") (pintype "bidirectional"))
    )
    (net (code "75") (name "TX_ESP") (class "Default")
      (node (ref "R2") (pin "P$1") (pinfunction "1_P$1") (pintype "passive"))
      (node (ref "U$13") (pin "U0TXD") (pinfunction "U0TXD_U0TXD") (pintype "bidirectional"))
      (node (ref "X1") (pin "16") (pinfunction "TXD_16") (pintype "output"))
    )
    (net (code "76") (name "VBAT") (class "Default")
      (node (ref "C8") (pin "P$1") (pinfunction "1_P$1") (pintype "passive"))
      (node (ref "IC3") (pin "3") (pinfunction "VBAT_3") (pintype "bidirectional"))
      (node (ref "J1") (pin "2") (pinfunction "+_2") (pintype "bidirectional"))
      (node (ref "R6") (pin "P$2") (pinfunction "2_P$2") (pintype "passive"))
      (node (ref "U$4") (pin "6") (pinfunction "IN2_6") (pintype "bidirectional"))
    )
    (net (code "77") (name "VBUS") (class "Default")
      (node (ref "C7") (pin "P$2") (pinfunction "2_P$2") (pintype "passive"))
      (node (ref "CHARGE") (pin "A") (pinfunction "A_A") (pintype "passive"))
      (node (ref "F1") (pin "2") (pinfunction "2_2") (pintype "bidirectional"))
      (node (ref "IC3") (pin "4") (pinfunction "VDD_4") (pintype "power_in"))
      (node (ref "U$4") (pin "8") (pinfunction "IN1_8") (pintype "bidirectional"))
    )
    (net (code "78") (name "VCC") (class "Default")
      (node (ref "C10") (pin "P$2") (pinfunction "2_P$2") (pintype "passive"))
      (node (ref "C11") (pin "P$2") (pinfunction "2_P$2") (pintype "passive"))
      (node (ref "C3") (pin "P$1") (pinfunction "1_P$1") (pintype "passive"))
      (node (ref "C4") (pin "P$1") (pinfunction "1_P$1") (pintype "passive"))
      (node (ref "C9") (pin "P$2") (pinfunction "2_P$2") (pintype "passive"))
      (node (ref "CH340G") (pin "16") (pinfunction "VCC_16") (pintype "bidirectional"))
      (node (ref "CH340G") (pin "4") (pinfunction "V3_4") (pintype "bidirectional"))
      (node (ref "IC1") (pin "16") (pinfunction "VDD_16") (pintype "power_in"))
      (node (ref "JP2") (pin "P$2") (pinfunction "2_P$2") (pintype "passive"))
      (node (ref "LED1") (pin "4") (pinfunction "A_4") (pintype "passive"))
      (node (ref "LED2") (pin "4") (pinfunction "A_4") (pintype "passive"))
      (node (ref "LED3") (pin "4") (pinfunction "A_4") (pintype "passive"))
      (node (ref "LED4") (pin "4") (pinfunction "A_4") (pintype "passive"))
      (node (ref "R1") (pin "P$2") (pinfunction "2_P$2") (pintype "passive"))
      (node (ref "R12") (pin "P$1") (pinfunction "1_P$1") (pintype "passive"))
      (node (ref "R13") (pin "P$1") (pinfunction "1_P$1") (pintype "passive"))
      (node (ref "RPU") (pin "1") (pinfunction "1_1") (pintype "passive"))
      (node (ref "RPU") (pin "2") (pinfunction "1_2") (pintype "passive"))
      (node (ref "RPU") (pin "3") (pinfunction "1_3") (pintype "passive"))
      (node (ref "RPU") (pin "4") (pinfunction "1_4") (pintype "passive"))
      (node (ref "S2") (pin "1") (pinfunction "O_1") (pintype "passive"))
      (node (ref "U$1") (pin "1") (pinfunction "VDD_1") (pintype "power_in"))
      (node (ref "U$1") (pin "6") (pinfunction "OSC_6") (pintype "passive"))
      (node (ref "U$10") (pin "P$2") (pinfunction "VCC_P$2") (pintype "bidirectional"))
      (node (ref "U$14") (pin "4") (pinfunction "VDD_4") (pintype "power_in"))
      (node (ref "U$2") (pin "8") (pinfunction "VCC_8") (pintype "bidirectional"))
      (node (ref "U$9") (pin "P$5") (pinfunction "VOUT_P$5") (pintype "bidirectional"))
      (node (ref "X1") (pin "8") (pinfunction "VCC_8") (pintype "power_in"))
    )
    (net (code "79") (name "VREG_IN") (class "Default")
      (node (ref "C2") (pin "P$1") (pinfunction "1_P$1") (pintype "passive"))
      (node (ref "U$4") (pin "7") (pinfunction "OUT_7") (pintype "bidirectional"))
      (node (ref "U$9") (pin "P$1") (pinfunction "VIN_P$1") (pintype "bidirectional"))
    )
    (net (code "80") (name "unconnected-(CH340G-CTS-Pad9)") (class "Default")
      (node (ref "CH340G") (pin "9") (pinfunction "CTS_9") (pintype "bidirectional"))
    )
    (net (code "81") (name "unconnected-(CH340G-DCD-Pad12)") (class "Default")
      (node (ref "CH340G") (pin "12") (pinfunction "DCD_12") (pintype "bidirectional"))
    )
    (net (code "82") (name "unconnected-(CH340G-DSR-Pad10)") (class "Default")
      (node (ref "CH340G") (pin "10") (pinfunction "DSR_10") (pintype "bidirectional"))
    )
    (net (code "83") (name "unconnected-(CH340G-RI-Pad11)") (class "Default")
      (node (ref "CH340G") (pin "11") (pinfunction "RI_11") (pintype "bidirectional"))
    )
    (net (code "84") (name "unconnected-(CH340G-RS232-Pad15)") (class "Default")
      (node (ref "CH340G") (pin "15") (pinfunction "RS232_15") (pintype "bidirectional"))
    )
    (net (code "85") (name "unconnected-(IC1-~{INT}-Pad13)") (class "Default")
      (node (ref "IC1") (pin "13") (pinfunction "~{INT}_13") (pintype "output"))
    )
    (net (code "86") (name "unconnected-(J1-PAD1-PadNC1)") (class "Default")
      (node (ref "J1") (pin "NC1") (pinfunction "PAD1_NC1") (pintype "bidirectional"))
    )
    (net (code "87") (name "unconnected-(J1-PAD2-PadNC2)") (class "Default")
      (node (ref "J1") (pin "NC2") (pinfunction "PAD2_NC2") (pintype "bidirectional"))
    )
    (net (code "88") (name "unconnected-(U$4-STAT-Pad1)") (class "Default")
      (node (ref "U$4") (pin "1") (pinfunction "STAT_1") (pintype "bidirectional"))
    )
    (net (code "89") (name "unconnected-(U$13-PadXTAL_IN)") (class "Default")
      (node (ref "U$13") (pin "XTAL_IN") (pinfunction "XTAL_IN_XTAL_IN") (pintype "bidirectional"))
    )
    (net (code "90") (name "unconnected-(U$13-PadXTAL_OUT)") (class "Default")
      (node (ref "U$13") (pin "XTAL_OUT") (pinfunction "XTAL_OUT_XTAL_OUT") (pintype "bidirectional"))
    )
    (net (code "91") (name "unconnected-(U$14-CARD_DETECT-Pad10)") (class "Default")
      (node (ref "U$14") (pin "10") (pinfunction "CARD_DETECT_10") (pintype "passive"))
    )
    (net (code "92") (name "unconnected-(U$14-COMMON_SW-Pad11)") (class "Default")
      (node (ref "U$14") (pin "11") (pinfunction "COMMON_SW_11") (pintype "passive"))
    )
    (net (code "93") (name "unconnected-(U$14-WRITE_PROTECT-Pad12)") (class "Default")
      (node (ref "U$14") (pin "12") (pinfunction "WRITE_PROTECT_12") (pintype "passive"))
    )
    (net (code "94") (name "unconnected-(U2-USBID-PadID1)") (class "Default")
      (node (ref "U2") (pin "ID1") (pinfunction "USBID_ID1") (pintype "bidirectional"))
    )
  )
)
